# Stabilizator.net
KiCad netlist of a schematic drawn in Altium Designer
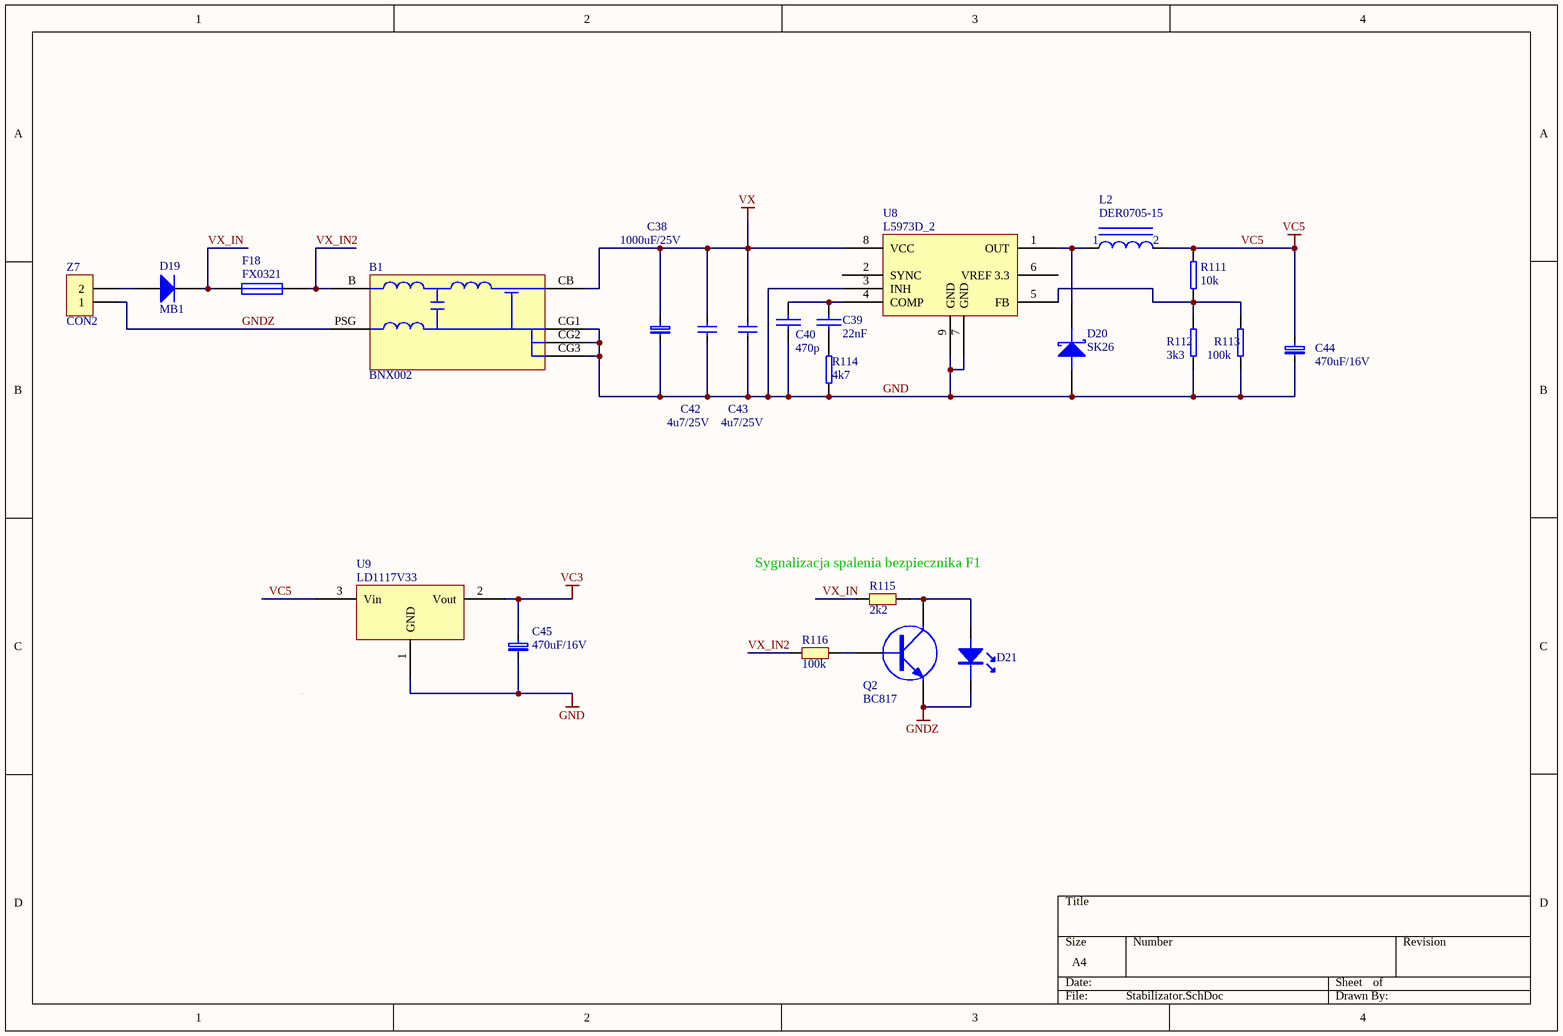
[diagram p0: Stabilizator.SchDoc]

(export (version "E")
  (design (tool "Eeschema 10.0.6"))
  (components
    (comp (ref "B1") (value "BNX002") (footprint "BNX002") (libsource (lib "ElhosSchLib") (part "BNX002")))
    (comp (ref "C38")
      (value "1000uF/25V")
      (footprint "RB-.2/.4")
      (description "KONDENSATOR ELEKTROLITYCZNY TANTALOWY SMD")
      (libsource (lib "*") (part "CAP_TANTAL_SMD"))
    )
    (comp (ref "C39")
      (value "22nF")
      (footprint "0603C")
      (description "Capacitor")
      (libsource (lib "") (part "CAP_1"))
    )
    (comp (ref "C40")
      (value "470p")
      (footprint "0603C")
      (description "Capacitor")
      (libsource (lib "") (part "CAP_1"))
    )
    (comp (ref "C42") (value "4u7/25V") (footprint "1206") (libsource (lib "*") (part "CAP")))
    (comp (ref "C43") (value "4u7/25V") (footprint "1206") (libsource (lib "*") (part "CAP")))
    (comp (ref "C44")
      (value "470uF/16V")
      (footprint "CAP_D")
      (description "KONDENSATOR ELEKTROLITYCZNY TANTALOWY SMD")
      (libsource (lib "*") (part "CAP_TANTAL_SMD"))
    )
    (comp (ref "C45")
      (value "470uF/16V")
      (footprint "CAP_D")
      (description "KONDENSATOR ELEKTROLITYCZNY TANTALOWY SMD")
      (libsource (lib "*") (part "CAP_TANTAL_SMD"))
    )
    (comp (ref "D19")
      (value "MB1")
      (footprint "RD5")
      (description "Default Diode")
      (fields (field (name "PUBLISHER") "Altium Limited"))
      (libsource (lib "Miscellaneous Devices") (part "Diode"))
    )
    (comp (ref "D20")
      (value "SK26")
      (footprint "RD5")
      (description "Schottky Diode")
      (libsource (lib "*") (part "DIODE SCHOTTKY"))
    )
    (comp (ref "D21") (value "LED1") (footprint "0805LR") (libsource (lib "ElhosSchLib") (part "LED1")))
    (comp (ref "F18")
      (value "FX0321")
      (footprint "FX300")
      (description "Fuse")
      (libsource (lib "*") (part "FUSE1"))
    )
    (comp (ref "L2") (value "DER0705-15") (footprint "DER0705_1") (libsource (lib "*") (part "CEWKA_1")))
    (comp (ref "Q2")
      (value "BC817")
      (footprint "SOT23-3Q")
      (description "NPN Transistor")
      (libsource (lib "*") (part "NPN-SOT23"))
    )
    (comp (ref "R111") (value "10k") (footprint "0603R") (libsource (lib "*") (part "RES3")))
    (comp (ref "R112") (value "3k3") (footprint "0603R") (libsource (lib "*") (part "RES3")))
    (comp (ref "R113") (value "100k") (footprint "0603R") (libsource (lib "*") (part "RES3")))
    (comp (ref "R114") (value "4k7") (footprint "0603R") (libsource (lib "*") (part "RES3")))
    (comp (ref "R115") (value "2k2") (footprint "0603R") (libsource (lib "") (part "RES3_1")))
    (comp (ref "R116") (value "100k") (footprint "0603R") (libsource (lib "") (part "RES3_1")))
    (comp (ref "U8") (value "L5973D_2") (footprint "SO8_M") (libsource (lib "ElhosSchLib") (part "L5973D_2")))
    (comp (ref "U9") (value "LD1117V33") (footprint "DPAK") (libsource (lib "*") (part "LD1117V33")))
    (comp (ref "Z7")
      (value "CON2")
      (footprint "ARC-2-5.08-A1")
      (description "Connector")
      (libsource (lib "*") (part "CON2"))
    )
  )
  (nets
    (net (code "1") (name "/VX_IN") (class "Default")
      (node (ref "D19") (pin "K") (pinfunction "K_K") (pintype "passive"))
      (node (ref "F18") (pin "1") (pinfunction "1_1") (pintype "passive"))
      (node (ref "R115") (pin "2") (pintype "passive"))
    )
    (net (code "2") (name "/VX_IN2") (class "Default")
      (node (ref "B1") (pin "B") (pintype "passive"))
      (node (ref "F18") (pin "2") (pinfunction "2_2") (pintype "passive"))
      (node (ref "R116") (pin "2") (pintype "passive"))
    )
    (net (code "3") (name "GND") (class "Default")
      (node (ref "B1") (pin "CG1") (pintype "passive"))
      (node (ref "B1") (pin "CG2") (pintype "passive"))
      (node (ref "B1") (pin "CG3") (pintype "passive"))
      (node (ref "C38") (pin "1") (pintype "passive"))
      (node (ref "C40") (pin "2") (pinfunction "2_2") (pintype "passive"))
      (node (ref "C42") (pin "1") (pintype "passive"))
      (node (ref "C43") (pin "1") (pintype "passive"))
      (node (ref "C44") (pin "1") (pintype "passive"))
      (node (ref "C45") (pin "1") (pintype "passive"))
      (node (ref "D20") (pin "A") (pinfunction "A_A") (pintype "passive"))
      (node (ref "R112") (pin "2") (pintype "passive"))
      (node (ref "R113") (pin "2") (pintype "passive"))
      (node (ref "R114") (pin "2") (pintype "passive"))
      (node (ref "U8") (pin "3") (pinfunction "INH_3") (pintype "passive"))
      (node (ref "U8") (pin "7") (pinfunction "GND_7") (pintype "passive"))
      (node (ref "U8") (pin "9") (pinfunction "GND_9") (pintype "passive"))
      (node (ref "U9") (pin "1") (pinfunction "GND_1") (pintype "passive"))
    )
    (net (code "4") (name "GNDZ") (class "Default")
      (node (ref "B1") (pin "PSG") (pintype "passive"))
      (node (ref "D21") (pin "K") (pinfunction "2_K") (pintype "passive"))
      (node (ref "Q2") (pin "E") (pinfunction "E_E") (pintype "passive"))
      (node (ref "Z7") (pin "1") (pinfunction "1_1") (pintype "passive"))
    )
    (net (code "5") (name "Net-(C39-Pad1)") (class "Default")
      (node (ref "C39") (pin "1") (pinfunction "1_1") (pintype "passive"))
      (node (ref "R114") (pin "1") (pintype "passive"))
    )
    (net (code "6") (name "Net-(D19-PadA)") (class "Default")
      (node (ref "D19") (pin "A") (pinfunction "A_A") (pintype "passive"))
      (node (ref "Z7") (pin "2") (pinfunction "2_2") (pintype "passive"))
    )
    (net (code "7") (name "Net-(D21-1)") (class "Default")
      (node (ref "D21") (pin "A") (pinfunction "1_A") (pintype "passive"))
      (node (ref "Q2") (pin "C") (pinfunction "C_C") (pintype "passive"))
      (node (ref "R115") (pin "1") (pintype "passive"))
    )
    (net (code "8") (name "Net-(Q2-PadB)") (class "Default")
      (node (ref "Q2") (pin "B") (pinfunction "B_B") (pintype "passive"))
      (node (ref "R116") (pin "1") (pintype "passive"))
    )
    (net (code "9") (name "Net-(U8-COMP)") (class "Default")
      (node (ref "C39") (pin "2") (pinfunction "2_2") (pintype "passive"))
      (node (ref "C40") (pin "1") (pinfunction "1_1") (pintype "passive"))
      (node (ref "U8") (pin "4") (pinfunction "COMP_4") (pintype "passive"))
    )
    (net (code "10") (name "Net-(U8-FB)") (class "Default")
      (node (ref "R111") (pin "2") (pintype "passive"))
      (node (ref "R112") (pin "1") (pintype "passive"))
      (node (ref "R113") (pin "1") (pintype "passive"))
      (node (ref "U8") (pin "5") (pinfunction "FB_5") (pintype "passive"))
    )
    (net (code "11") (name "Net-(U8-OUT)") (class "Default")
      (node (ref "D20") (pin "K") (pinfunction "K_K") (pintype "passive"))
      (node (ref "L2") (pin "1") (pintype "passive"))
      (node (ref "U8") (pin "1") (pinfunction "OUT_1") (pintype "passive"))
    )
    (net (code "12") (name "VC3") (class "Default")
      (node (ref "C45") (pin "2") (pintype "passive"))
      (node (ref "U9") (pin "2") (pinfunction "Vout_2") (pintype "passive"))
    )
    (net (code "13") (name "VC5") (class "Default")
      (node (ref "C44") (pin "2") (pintype "passive"))
      (node (ref "L2") (pin "2") (pintype "passive"))
      (node (ref "R111") (pin "1") (pintype "passive"))
      (node (ref "U9") (pin "3") (pinfunction "Vin_3") (pintype "passive"))
    )
    (net (code "14") (name "VX") (class "Default")
      (node (ref "B1") (pin "CB") (pintype "passive"))
      (node (ref "C38") (pin "2") (pintype "passive"))
      (node (ref "C42") (pin "2") (pintype "passive"))
      (node (ref "C43") (pin "2") (pintype "passive"))
      (node (ref "U8") (pin "8") (pinfunction "VCC_8") (pintype "passive"))
    )
    (net (code "15") (name "unconnected-(U8-SYNC-Pad2)") (class "Default")
      (node (ref "U8") (pin "2") (pinfunction "SYNC_2") (pintype "passive"))
    )
    (net (code "16") (name "unconnected-(U8-VREF_3.3-Pad6)") (class "Default")
      (node (ref "U8") (pin "6") (pinfunction "VREF_3.3_6") (pintype "passive"))
    )
  )
)
